# PMIC.net
KiCad netlist of a schematic drawn in Altium Designer
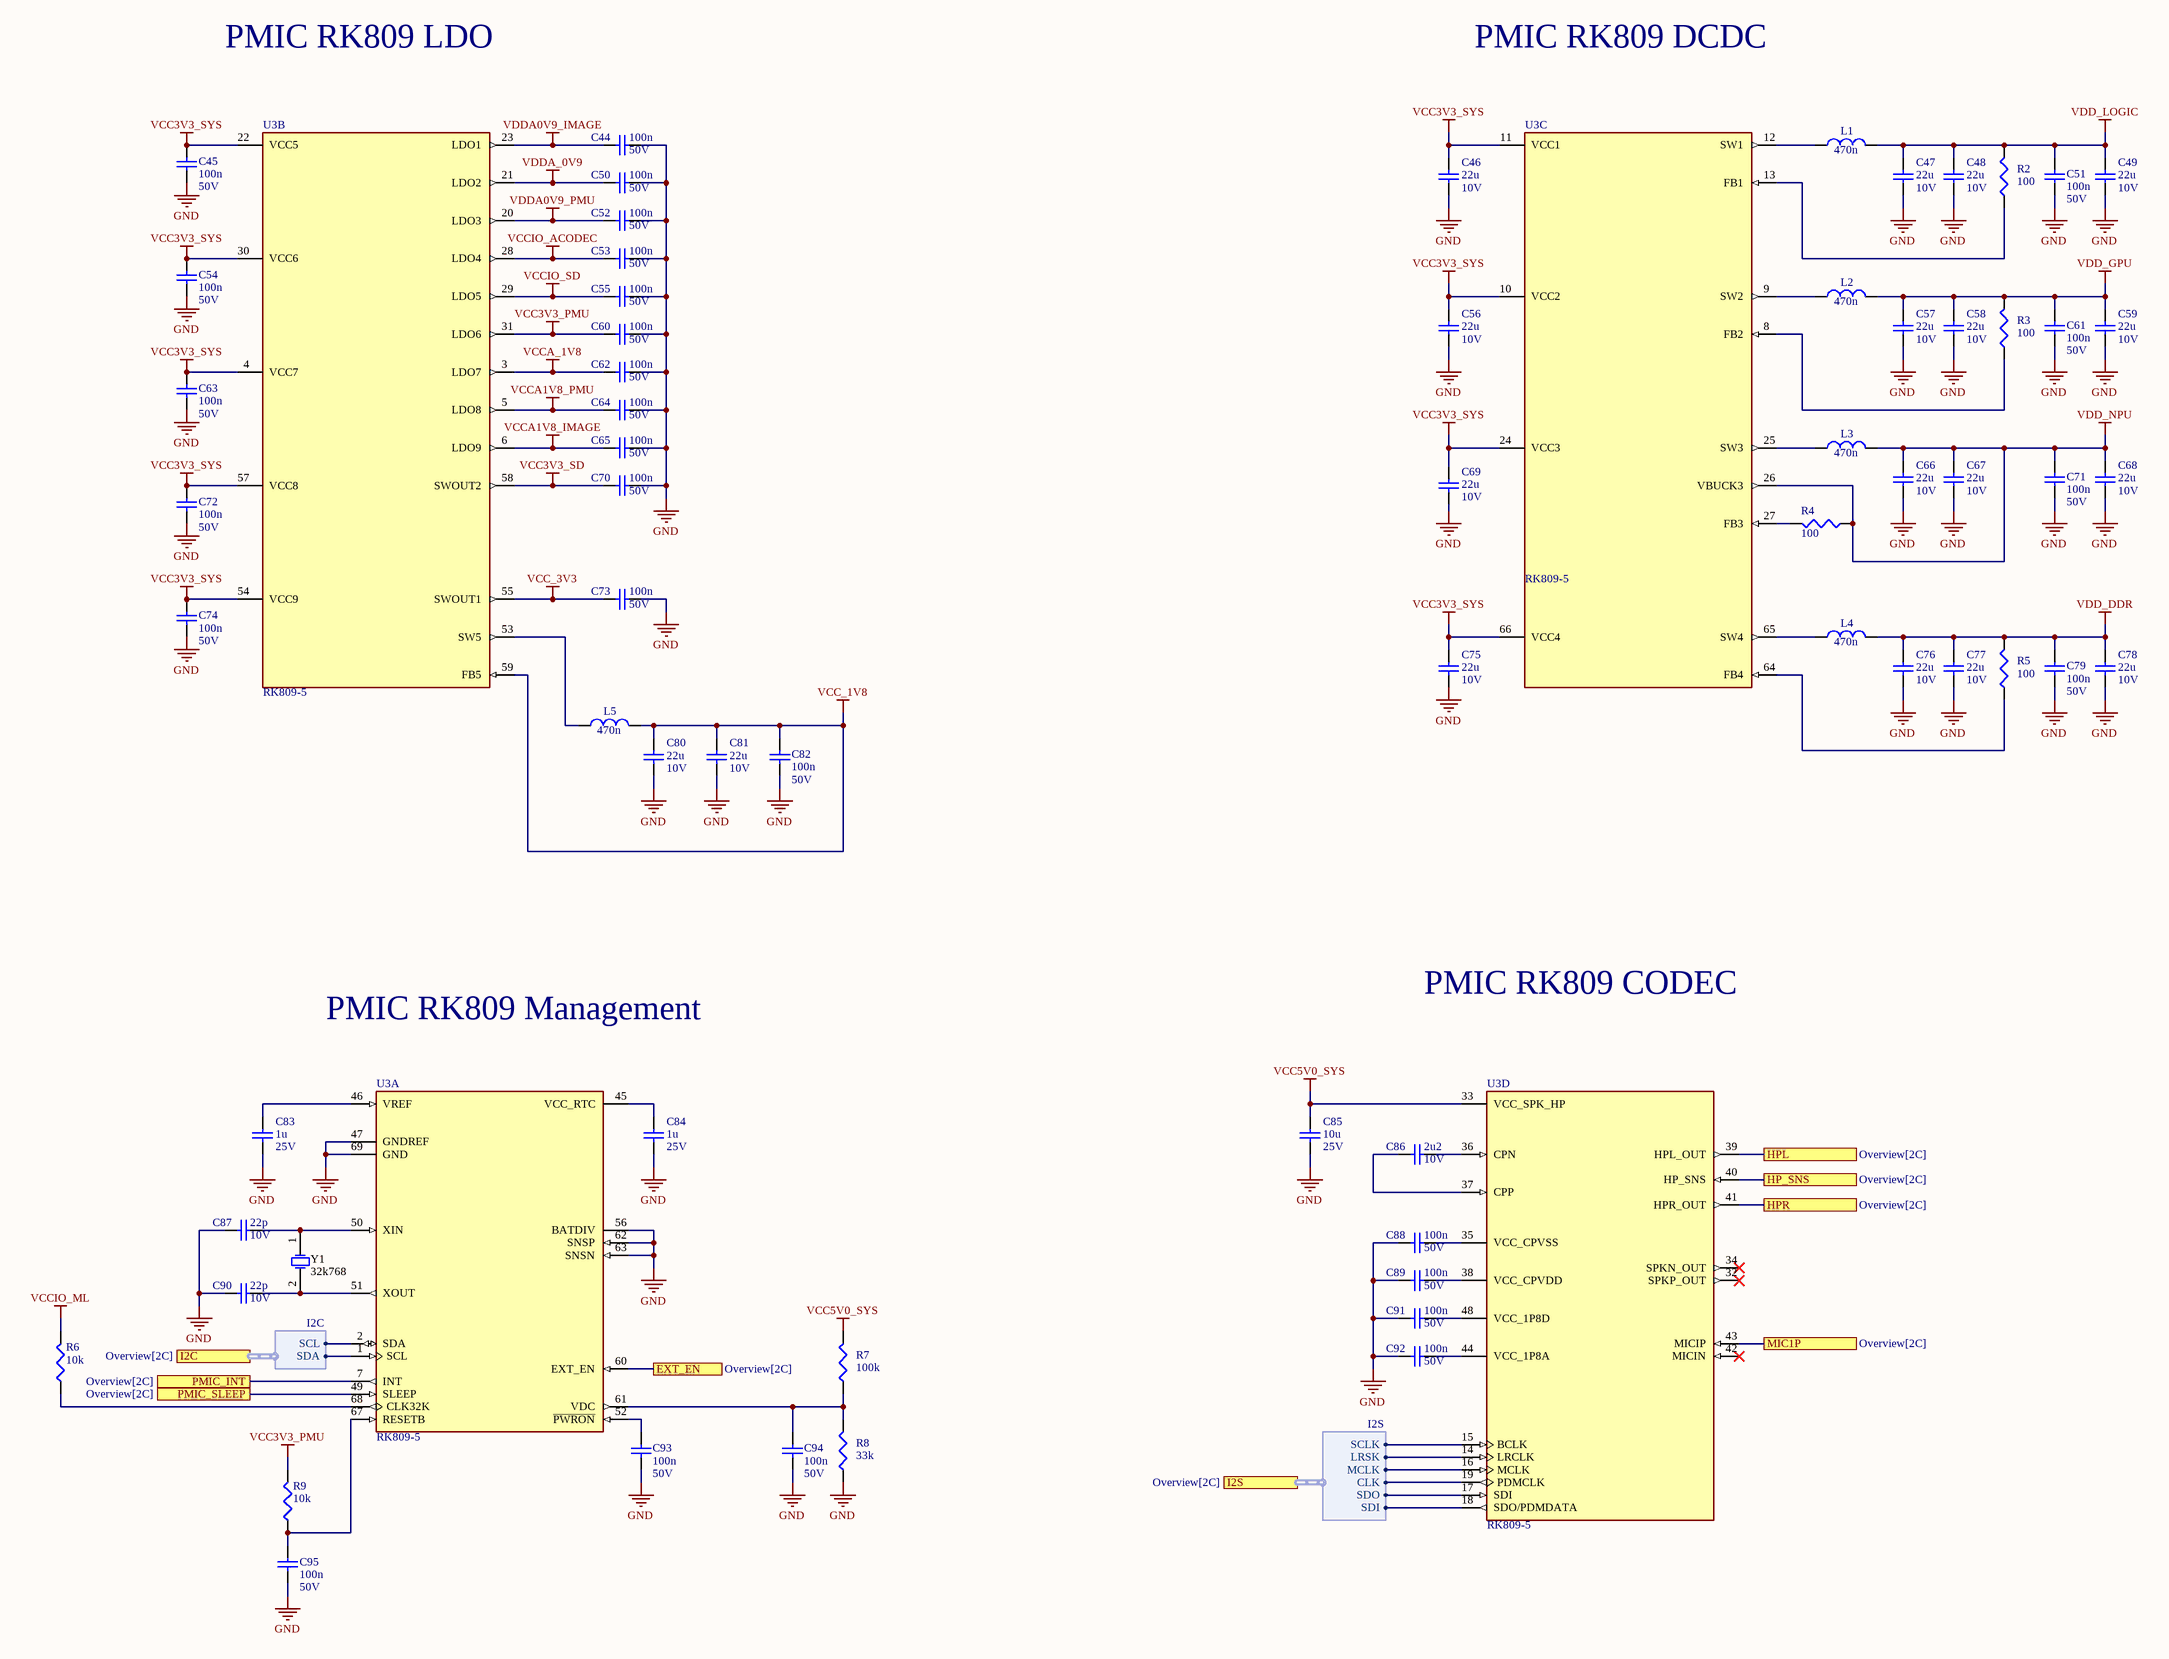
[diagram p0: PMIC.SchDoc]

(export (version "E")
  (design (tool "Eeschema 10.0.6"))
  (components
    (comp (ref "C44")
      (value "100n")
      (footprint "GRM155R71H104KE14D")
      (description "CAP 100N 50V X7R 0402")
      (fields (field (name "VOLTAGE") "50V") (field (name "Comment") "GRM155R71H104KE14D"))
      (libsource (lib "PersonalAltiumLibrary") (part "GRM155R71H104KE14D"))
    )
    (comp (ref "C45")
      (value "100n")
      (footprint "GRM155R71H104KE14D")
      (description "CAP 100N 50V X7R 0402")
      (fields (field (name "VOLTAGE") "50V") (field (name "Comment") "GRM155R71H104KE14D"))
      (libsource (lib "PersonalAltiumLibrary") (part "GRM155R71H104KE14D"))
    )
    (comp (ref "C46")
      (value "22u")
      (footprint "GRM188R61A226ME15D")
      (description "CAP 22U 10V X5R 0603")
      (fields (field (name "VOLTAGE") "10V") (field (name "Comment") "GRM188R61A226ME15D"))
      (libsource (lib "PersonalAltiumLibrary") (part "GRM188R61A226ME15D"))
    )
    (comp (ref "C47")
      (value "22u")
      (footprint "GRM188R61A226ME15D")
      (description "CAP 22U 10V X5R 0603")
      (fields (field (name "VOLTAGE") "10V") (field (name "Comment") "GRM188R61A226ME15D"))
      (libsource (lib "PersonalAltiumLibrary") (part "GRM188R61A226ME15D"))
    )
    (comp (ref "C48")
      (value "22u")
      (footprint "GRM188R61A226ME15D")
      (description "CAP 22U 10V X5R 0603")
      (fields (field (name "VOLTAGE") "10V") (field (name "Comment") "GRM188R61A226ME15D"))
      (libsource (lib "PersonalAltiumLibrary") (part "GRM188R61A226ME15D"))
    )
    (comp (ref "C49")
      (value "22u")
      (footprint "GRM188R61A226ME15D")
      (description "CAP 22U 10V X5R 0603")
      (fields (field (name "VOLTAGE") "10V") (field (name "Comment") "GRM188R61A226ME15D"))
      (libsource (lib "PersonalAltiumLibrary") (part "GRM188R61A226ME15D"))
    )
    (comp (ref "C50")
      (value "100n")
      (footprint "GRM155R71H104KE14D")
      (description "CAP 100N 50V X7R 0402")
      (fields (field (name "VOLTAGE") "50V") (field (name "Comment") "GRM155R71H104KE14D"))
      (libsource (lib "PersonalAltiumLibrary") (part "GRM155R71H104KE14D"))
    )
    (comp (ref "C51")
      (value "100n")
      (footprint "GRM155R71H104KE14D")
      (description "CAP 100N 50V X7R 0402")
      (fields (field (name "VOLTAGE") "50V") (field (name "Comment") "GRM155R71H104KE14D"))
      (libsource (lib "PersonalAltiumLibrary") (part "GRM155R71H104KE14D"))
    )
    (comp (ref "C52")
      (value "100n")
      (footprint "GRM155R71H104KE14D")
      (description "CAP 100N 50V X7R 0402")
      (fields (field (name "VOLTAGE") "50V") (field (name "Comment") "GRM155R71H104KE14D"))
      (libsource (lib "PersonalAltiumLibrary") (part "GRM155R71H104KE14D"))
    )
    (comp (ref "C53")
      (value "100n")
      (footprint "GRM155R71H104KE14D")
      (description "CAP 100N 50V X7R 0402")
      (fields (field (name "VOLTAGE") "50V") (field (name "Comment") "GRM155R71H104KE14D"))
      (libsource (lib "PersonalAltiumLibrary") (part "GRM155R71H104KE14D"))
    )
    (comp (ref "C54")
      (value "100n")
      (footprint "GRM155R71H104KE14D")
      (description "CAP 100N 50V X7R 0402")
      (fields (field (name "VOLTAGE") "50V") (field (name "Comment") "GRM155R71H104KE14D"))
      (libsource (lib "PersonalAltiumLibrary") (part "GRM155R71H104KE14D"))
    )
    (comp (ref "C55")
      (value "100n")
      (footprint "GRM155R71H104KE14D")
      (description "CAP 100N 50V X7R 0402")
      (fields (field (name "VOLTAGE") "50V") (field (name "Comment") "GRM155R71H104KE14D"))
      (libsource (lib "PersonalAltiumLibrary") (part "GRM155R71H104KE14D"))
    )
    (comp (ref "C56")
      (value "22u")
      (footprint "GRM188R61A226ME15D")
      (description "CAP 22U 10V X5R 0603")
      (fields (field (name "VOLTAGE") "10V") (field (name "Comment") "GRM188R61A226ME15D"))
      (libsource (lib "PersonalAltiumLibrary") (part "GRM188R61A226ME15D"))
    )
    (comp (ref "C57")
      (value "22u")
      (footprint "GRM188R61A226ME15D")
      (description "CAP 22U 10V X5R 0603")
      (fields (field (name "VOLTAGE") "10V") (field (name "Comment") "GRM188R61A226ME15D"))
      (libsource (lib "PersonalAltiumLibrary") (part "GRM188R61A226ME15D"))
    )
    (comp (ref "C58")
      (value "22u")
      (footprint "GRM188R61A226ME15D")
      (description "CAP 22U 10V X5R 0603")
      (fields (field (name "VOLTAGE") "10V") (field (name "Comment") "GRM188R61A226ME15D"))
      (libsource (lib "PersonalAltiumLibrary") (part "GRM188R61A226ME15D"))
    )
    (comp (ref "C59")
      (value "22u")
      (footprint "GRM188R61A226ME15D")
      (description "CAP 22U 10V X5R 0603")
      (fields (field (name "VOLTAGE") "10V") (field (name "Comment") "GRM188R61A226ME15D"))
      (libsource (lib "PersonalAltiumLibrary") (part "GRM188R61A226ME15D"))
    )
    (comp (ref "C60")
      (value "100n")
      (footprint "GRM155R71H104KE14D")
      (description "CAP 100N 50V X7R 0402")
      (fields (field (name "VOLTAGE") "50V") (field (name "Comment") "GRM155R71H104KE14D"))
      (libsource (lib "PersonalAltiumLibrary") (part "GRM155R71H104KE14D"))
    )
    (comp (ref "C61")
      (value "100n")
      (footprint "GRM155R71H104KE14D")
      (description "CAP 100N 50V X7R 0402")
      (fields (field (name "VOLTAGE") "50V") (field (name "Comment") "GRM155R71H104KE14D"))
      (libsource (lib "PersonalAltiumLibrary") (part "GRM155R71H104KE14D"))
    )
    (comp (ref "C62")
      (value "100n")
      (footprint "GRM155R71H104KE14D")
      (description "CAP 100N 50V X7R 0402")
      (fields (field (name "VOLTAGE") "50V") (field (name "Comment") "GRM155R71H104KE14D"))
      (libsource (lib "PersonalAltiumLibrary") (part "GRM155R71H104KE14D"))
    )
    (comp (ref "C63")
      (value "100n")
      (footprint "GRM155R71H104KE14D")
      (description "CAP 100N 50V X7R 0402")
      (fields (field (name "VOLTAGE") "50V") (field (name "Comment") "GRM155R71H104KE14D"))
      (libsource (lib "PersonalAltiumLibrary") (part "GRM155R71H104KE14D"))
    )
    (comp (ref "C64")
      (value "100n")
      (footprint "GRM155R71H104KE14D")
      (description "CAP 100N 50V X7R 0402")
      (fields (field (name "VOLTAGE") "50V") (field (name "Comment") "GRM155R71H104KE14D"))
      (libsource (lib "PersonalAltiumLibrary") (part "GRM155R71H104KE14D"))
    )
    (comp (ref "C65")
      (value "100n")
      (footprint "GRM155R71H104KE14D")
      (description "CAP 100N 50V X7R 0402")
      (fields (field (name "VOLTAGE") "50V") (field (name "Comment") "GRM155R71H104KE14D"))
      (libsource (lib "PersonalAltiumLibrary") (part "GRM155R71H104KE14D"))
    )
    (comp (ref "C66")
      (value "22u")
      (footprint "GRM188R61A226ME15D")
      (description "CAP 22U 10V X5R 0603")
      (fields (field (name "VOLTAGE") "10V") (field (name "Comment") "GRM188R61A226ME15D"))
      (libsource (lib "PersonalAltiumLibrary") (part "GRM188R61A226ME15D"))
    )
    (comp (ref "C67")
      (value "22u")
      (footprint "GRM188R61A226ME15D")
      (description "CAP 22U 10V X5R 0603")
      (fields (field (name "VOLTAGE") "10V") (field (name "Comment") "GRM188R61A226ME15D"))
      (libsource (lib "PersonalAltiumLibrary") (part "GRM188R61A226ME15D"))
    )
    (comp (ref "C68")
      (value "22u")
      (footprint "GRM188R61A226ME15D")
      (description "CAP 22U 10V X5R 0603")
      (fields (field (name "VOLTAGE") "10V") (field (name "Comment") "GRM188R61A226ME15D"))
      (libsource (lib "PersonalAltiumLibrary") (part "GRM188R61A226ME15D"))
    )
    (comp (ref "C69")
      (value "22u")
      (footprint "GRM188R61A226ME15D")
      (description "CAP 22U 10V X5R 0603")
      (fields (field (name "VOLTAGE") "10V") (field (name "Comment") "GRM188R61A226ME15D"))
      (libsource (lib "PersonalAltiumLibrary") (part "GRM188R61A226ME15D"))
    )
    (comp (ref "C70")
      (value "100n")
      (footprint "GRM155R71H104KE14D")
      (description "CAP 100N 50V X7R 0402")
      (fields (field (name "VOLTAGE") "50V") (field (name "Comment") "GRM155R71H104KE14D"))
      (libsource (lib "PersonalAltiumLibrary") (part "GRM155R71H104KE14D"))
    )
    (comp (ref "C71")
      (value "100n")
      (footprint "GRM155R71H104KE14D")
      (description "CAP 100N 50V X7R 0402")
      (fields (field (name "VOLTAGE") "50V") (field (name "Comment") "GRM155R71H104KE14D"))
      (libsource (lib "PersonalAltiumLibrary") (part "GRM155R71H104KE14D"))
    )
    (comp (ref "C72")
      (value "100n")
      (footprint "GRM155R71H104KE14D")
      (description "CAP 100N 50V X7R 0402")
      (fields (field (name "VOLTAGE") "50V") (field (name "Comment") "GRM155R71H104KE14D"))
      (libsource (lib "PersonalAltiumLibrary") (part "GRM155R71H104KE14D"))
    )
    (comp (ref "C73")
      (value "100n")
      (footprint "GRM155R71H104KE14D")
      (description "CAP 100N 50V X7R 0402")
      (fields (field (name "VOLTAGE") "50V") (field (name "Comment") "GRM155R71H104KE14D"))
      (libsource (lib "PersonalAltiumLibrary") (part "GRM155R71H104KE14D"))
    )
    (comp (ref "C74")
      (value "100n")
      (footprint "GRM155R71H104KE14D")
      (description "CAP 100N 50V X7R 0402")
      (fields (field (name "VOLTAGE") "50V") (field (name "Comment") "GRM155R71H104KE14D"))
      (libsource (lib "PersonalAltiumLibrary") (part "GRM155R71H104KE14D"))
    )
    (comp (ref "C75")
      (value "22u")
      (footprint "GRM188R61A226ME15D")
      (description "CAP 22U 10V X5R 0603")
      (fields (field (name "VOLTAGE") "10V") (field (name "Comment") "GRM188R61A226ME15D"))
      (libsource (lib "PersonalAltiumLibrary") (part "GRM188R61A226ME15D"))
    )
    (comp (ref "C76")
      (value "22u")
      (footprint "GRM188R61A226ME15D")
      (description "CAP 22U 10V X5R 0603")
      (fields (field (name "VOLTAGE") "10V") (field (name "Comment") "GRM188R61A226ME15D"))
      (libsource (lib "PersonalAltiumLibrary") (part "GRM188R61A226ME15D"))
    )
    (comp (ref "C77")
      (value "22u")
      (footprint "GRM188R61A226ME15D")
      (description "CAP 22U 10V X5R 0603")
      (fields (field (name "VOLTAGE") "10V") (field (name "Comment") "GRM188R61A226ME15D"))
      (libsource (lib "PersonalAltiumLibrary") (part "GRM188R61A226ME15D"))
    )
    (comp (ref "C78")
      (value "22u")
      (footprint "GRM188R61A226ME15D")
      (description "CAP 22U 10V X5R 0603")
      (fields (field (name "VOLTAGE") "10V") (field (name "Comment") "GRM188R61A226ME15D"))
      (libsource (lib "PersonalAltiumLibrary") (part "GRM188R61A226ME15D"))
    )
    (comp (ref "C79")
      (value "100n")
      (footprint "GRM155R71H104KE14D")
      (description "CAP 100N 50V X7R 0402")
      (fields (field (name "VOLTAGE") "50V") (field (name "Comment") "GRM155R71H104KE14D"))
      (libsource (lib "PersonalAltiumLibrary") (part "GRM155R71H104KE14D"))
    )
    (comp (ref "C80")
      (value "22u")
      (footprint "GRM188R61A226ME15D")
      (description "CAP 22U 10V X5R 0603")
      (fields (field (name "VOLTAGE") "10V") (field (name "Comment") "GRM188R61A226ME15D"))
      (libsource (lib "PersonalAltiumLibrary") (part "GRM188R61A226ME15D"))
    )
    (comp (ref "C81")
      (value "22u")
      (footprint "GRM188R61A226ME15D")
      (description "CAP 22U 10V X5R 0603")
      (fields (field (name "VOLTAGE") "10V") (field (name "Comment") "GRM188R61A226ME15D"))
      (libsource (lib "PersonalAltiumLibrary") (part "GRM188R61A226ME15D"))
    )
    (comp (ref "C82")
      (value "100n")
      (footprint "GRM155R71H104KE14D")
      (description "CAP 100N 50V X7R 0402")
      (fields (field (name "VOLTAGE") "50V") (field (name "Comment") "GRM155R71H104KE14D"))
      (libsource (lib "PersonalAltiumLibrary") (part "GRM155R71H104KE14D"))
    )
    (comp (ref "C83")
      (value "1u")
      (footprint "GRM155R61E105KA12D")
      (description "CAP 1U 25V X5R 0402")
      (fields (field (name "VOLTAGE") "25V") (field (name "Comment") "GRM155R61E105KA12D"))
      (libsource (lib "PersonalAltiumLibrary") (part "GRM155R61E105KA12D"))
    )
    (comp (ref "C84")
      (value "1u")
      (footprint "GRM155R61E105KA12D")
      (description "CAP 1U 25V X5R 0402")
      (fields (field (name "VOLTAGE") "25V") (field (name "Comment") "GRM155R61E105KA12D"))
      (libsource (lib "PersonalAltiumLibrary") (part "GRM155R61E105KA12D"))
    )
    (comp (ref "C85")
      (value "10u")
      (description "CAP 10U 25V X5R 0603")
      (fields (field (name "VOLTAGE") "25V") (field (name "Comment") "GRM188R61E106MA73D"))
      (libsource (lib "PersonalAltiumLibrary") (part "GRM188R61E106MA73D"))
    )
    (comp (ref "C86")
      (value "2u2")
      (footprint "GRM155R60J475ME47D")
      (description "CAP 2.2U 6.3V X5R 0402")
      (fields (field (name "VOLTAGE") "10V") (field (name "Comment") "Capacitor 2u2"))
      (libsource (lib "PersonalAltiumLibrary") (part "Capacitor 2u2"))
    )
    (comp (ref "C87")
      (value "22p")
      (footprint "GRM155R60J475ME47D")
      (description "CAP 22P 6.3V X5R 0402")
      (fields (field (name "VOLTAGE") "10V") (field (name "Comment") "CAP 22P"))
      (libsource (lib "PersonalAltiumLibrary") (part "CAP 22P"))
    )
    (comp (ref "C88")
      (value "100n")
      (footprint "GRM155R71H104KE14D")
      (description "CAP 100N 50V X7R 0402")
      (fields (field (name "VOLTAGE") "50V") (field (name "Comment") "GRM155R71H104KE14D"))
      (libsource (lib "PersonalAltiumLibrary") (part "GRM155R71H104KE14D"))
    )
    (comp (ref "C89")
      (value "100n")
      (footprint "GRM155R71H104KE14D")
      (description "CAP 100N 50V X7R 0402")
      (fields (field (name "VOLTAGE") "50V") (field (name "Comment") "GRM155R71H104KE14D"))
      (libsource (lib "PersonalAltiumLibrary") (part "GRM155R71H104KE14D"))
    )
    (comp (ref "C90")
      (value "22p")
      (footprint "GRM155R60J475ME47D")
      (description "CAP 22P 6.3V X5R 0402")
      (fields (field (name "VOLTAGE") "10V") (field (name "Comment") "CAP 22P"))
      (libsource (lib "PersonalAltiumLibrary") (part "CAP 22P"))
    )
    (comp (ref "C91")
      (value "100n")
      (footprint "GRM155R71H104KE14D")
      (description "CAP 100N 50V X7R 0402")
      (fields (field (name "VOLTAGE") "50V") (field (name "Comment") "GRM155R71H104KE14D"))
      (libsource (lib "PersonalAltiumLibrary") (part "GRM155R71H104KE14D"))
    )
    (comp (ref "C92")
      (value "100n")
      (footprint "GRM155R71H104KE14D")
      (description "CAP 100N 50V X7R 0402")
      (fields (field (name "VOLTAGE") "50V") (field (name "Comment") "GRM155R71H104KE14D"))
      (libsource (lib "PersonalAltiumLibrary") (part "GRM155R71H104KE14D"))
    )
    (comp (ref "C93")
      (value "100n")
      (footprint "GRM155R71H104KE14D")
      (description "CAP 100N 50V X7R 0402")
      (fields (field (name "VOLTAGE") "50V") (field (name "Comment") "GRM155R71H104KE14D"))
      (libsource (lib "PersonalAltiumLibrary") (part "GRM155R71H104KE14D"))
    )
    (comp (ref "C94")
      (value "100n")
      (footprint "GRM155R71H104KE14D")
      (description "CAP 100N 50V X7R 0402")
      (fields (field (name "VOLTAGE") "50V") (field (name "Comment") "GRM155R71H104KE14D"))
      (libsource (lib "PersonalAltiumLibrary") (part "GRM155R71H104KE14D"))
    )
    (comp (ref "C95")
      (value "100n")
      (footprint "GRM155R71H104KE14D")
      (description "CAP 100N 50V X7R 0402")
      (fields (field (name "VOLTAGE") "50V") (field (name "Comment") "GRM155R71H104KE14D"))
      (libsource (lib "PersonalAltiumLibrary") (part "GRM155R71H104KE14D"))
    )
    (comp (ref "L1")
      (value "470n")
      (description "IND 470N 4.05A 0806")
      (fields (field (name "Comment") "MCS20FC-R47MHC"))
      (libsource (lib "PersonalAltiumLibrary") (part "MCS20FC-R47MHC"))
    )
    (comp (ref "L2")
      (value "470n")
      (description "IND 470N 4.05A 0806")
      (fields (field (name "Comment") "MCS20FC-R47MHC"))
      (libsource (lib "PersonalAltiumLibrary") (part "MCS20FC-R47MHC"))
    )
    (comp (ref "L3")
      (value "470n")
      (description "IND 470N 4.05A 0806")
      (fields (field (name "Comment") "MCS20FC-R47MHC"))
      (libsource (lib "PersonalAltiumLibrary") (part "MCS20FC-R47MHC"))
    )
    (comp (ref "L4")
      (value "470n")
      (description "IND 470N 4.05A 0806")
      (fields (field (name "Comment") "MCS20FC-R47MHC"))
      (libsource (lib "PersonalAltiumLibrary") (part "MCS20FC-R47MHC"))
    )
    (comp (ref "L5")
      (value "470n")
      (description "IND 470N 4.05A 0806")
      (fields (field (name "Comment") "MCS20FC-R47MHC"))
      (libsource (lib "PersonalAltiumLibrary") (part "MCS20FC-R47MHC"))
    )
    (comp (ref "R2")
      (value "100")
      (footprint "RC0402FR-07100RL")
      (description "RES 100 1% 0402")
      (fields (field (name "Comment") "RC0402FR-07100RL"))
      (libsource (lib "PersonalAltiumLibrary") (part "RC0402FR-07100RL"))
    )
    (comp (ref "R3")
      (value "100")
      (footprint "RC0402FR-07100RL")
      (description "RES 100 1% 0402")
      (fields (field (name "Comment") "RC0402FR-07100RL"))
      (libsource (lib "PersonalAltiumLibrary") (part "RC0402FR-07100RL"))
    )
    (comp (ref "R4")
      (value "100")
      (footprint "RC0402FR-07100RL")
      (description "RES 100 1% 0402")
      (fields (field (name "Comment") "RC0402FR-07100RL"))
      (libsource (lib "PersonalAltiumLibrary") (part "RC0402FR-07100RL"))
    )
    (comp (ref "R5")
      (value "100")
      (footprint "RC0402FR-07100RL")
      (description "RES 100 1% 0402")
      (fields (field (name "Comment") "RC0402FR-07100RL"))
      (libsource (lib "PersonalAltiumLibrary") (part "RC0402FR-07100RL"))
    )
    (comp (ref "R6")
      (value "10k")
      (footprint "RC0402FR-0718KL")
      (description "RES 10k 1% 62.5mW 0402")
      (fields (field (name "Comment") "RES 10k"))
      (libsource (lib "PersonalAltiumLibrary") (part "RES 10k"))
    )
    (comp (ref "R7")
      (value "100k")
      (footprint "RC0402FR-07100KL")
      (description "RES 100k 1% 62.5mW 0402")
      (fields (field (name "Comment") "RC0402FR-07100KL"))
      (libsource (lib "PersonalAltiumLibrary") (part "RC0402FR-07100KL"))
    )
    (comp (ref "R8")
      (value "33k")
      (footprint "RC0402FR-07100KL")
      (description "RES 33k 1% 62.5mW 0402")
      (fields (field (name "Comment") "RES 33k"))
      (libsource (lib "PersonalAltiumLibrary") (part "RES 33k"))
    )
    (comp (ref "R9")
      (value "10k")
      (footprint "RC0402FR-0718KL")
      (description "RES 10k 1% 62.5mW 0402")
      (fields (field (name "Comment") "RES 10k"))
      (libsource (lib "PersonalAltiumLibrary") (part "RES 10k"))
    )
    (comp (ref "U3")
      (value "RK809-5")
      (footprint "RK809-5")
      (fields (field (name "MF") "Fuzhou Rockchip Electronics Co") (field (name "MP") "RK809-1"))
      (libsource (lib "PersonalAltiumLibrary") (part "RK809-5"))
    )
    (comp (ref "Y1") (value "32k768") (libsource (lib "PersonalAltiumLibrary") (part "32.768 Crystal")))
  )
  (nets
    (net (code "3") (name "/CLK") (class "Default")
      (node (ref "U3") (pin "19") (pinfunction "PDMCLK_19") (pintype "output"))
    )
    (net (code "4") (name "/EXT_EN") (class "Default")
      (node (ref "U3") (pin "60") (pinfunction "EXT_EN_60") (pintype "input"))
    )
    (net (code "5") (name "/HPL") (class "Default")
      (node (ref "U3") (pin "39") (pinfunction "HPL_OUT_39") (pintype "output"))
    )
    (net (code "6") (name "/HPR") (class "Default")
      (node (ref "U3") (pin "41") (pinfunction "HPR_OUT_41") (pintype "output"))
    )
    (net (code "7") (name "/HP_SNS") (class "Default")
      (node (ref "U3") (pin "40") (pinfunction "HP_SNS_40") (pintype "input"))
    )
    (net (code "8") (name "/LRSK") (class "Default")
      (node (ref "U3") (pin "14") (pinfunction "LRCLK_14") (pintype "input"))
    )
    (net (code "9") (name "/MCLK") (class "Default")
      (node (ref "U3") (pin "16") (pinfunction "MCLK_16") (pintype "input"))
    )
    (net (code "10") (name "/MIC1P") (class "Default")
      (node (ref "U3") (pin "43") (pinfunction "MICIP_43") (pintype "input"))
    )
    (net (code "11") (name "/PMIC_INT") (class "Default")
      (node (ref "U3") (pin "7") (pinfunction "INT_7") (pintype "output"))
    )
    (net (code "12") (name "/PMIC_SLEEP") (class "Default")
      (node (ref "U3") (pin "49") (pinfunction "SLEEP_49") (pintype "input"))
    )
    (net (code "13") (name "/SCL") (class "Default")
      (node (ref "U3") (pin "2") (pinfunction "SDA_2") (pintype "bidirectional"))
    )
    (net (code "14") (name "/SCLK") (class "Default")
      (node (ref "U3") (pin "15") (pinfunction "BCLK_15") (pintype "input"))
    )
    (net (code "15") (name "/SDA") (class "Default")
      (node (ref "U3") (pin "1") (pinfunction "SCL_1") (pintype "input"))
    )
    (net (code "16") (name "/SDI") (class "Default")
      (node (ref "U3") (pin "18") (pinfunction "SDO/PDMDATA_18") (pintype "output"))
    )
    (net (code "17") (name "/SDO") (class "Default")
      (node (ref "U3") (pin "17") (pinfunction "SDI_17") (pintype "input"))
    )
    (net (code "20") (name "GND") (class "Default")
      (node (ref "C44") (pin "2") (pinfunction "2_2") (pintype "passive"))
      (node (ref "C45") (pin "1") (pinfunction "1_1") (pintype "passive"))
      (node (ref "C46") (pin "2") (pinfunction "2_2") (pintype "passive"))
      (node (ref "C47") (pin "2") (pinfunction "2_2") (pintype "passive"))
      (node (ref "C48") (pin "2") (pinfunction "2_2") (pintype "passive"))
      (node (ref "C49") (pin "2") (pinfunction "2_2") (pintype "passive"))
      (node (ref "C50") (pin "2") (pinfunction "2_2") (pintype "passive"))
      (node (ref "C51") (pin "2") (pinfunction "2_2") (pintype "passive"))
      (node (ref "C52") (pin "2") (pinfunction "2_2") (pintype "passive"))
      (node (ref "C53") (pin "2") (pinfunction "2_2") (pintype "passive"))
      (node (ref "C54") (pin "1") (pinfunction "1_1") (pintype "passive"))
      (node (ref "C55") (pin "2") (pinfunction "2_2") (pintype "passive"))
      (node (ref "C56") (pin "2") (pinfunction "2_2") (pintype "passive"))
      (node (ref "C57") (pin "2") (pinfunction "2_2") (pintype "passive"))
      (node (ref "C58") (pin "2") (pinfunction "2_2") (pintype "passive"))
      (node (ref "C59") (pin "2") (pinfunction "2_2") (pintype "passive"))
      (node (ref "C60") (pin "2") (pinfunction "2_2") (pintype "passive"))
      (node (ref "C61") (pin "2") (pinfunction "2_2") (pintype "passive"))
      (node (ref "C62") (pin "2") (pinfunction "2_2") (pintype "passive"))
      (node (ref "C63") (pin "1") (pinfunction "1_1") (pintype "passive"))
      (node (ref "C64") (pin "2") (pinfunction "2_2") (pintype "passive"))
      (node (ref "C65") (pin "2") (pinfunction "2_2") (pintype "passive"))
      (node (ref "C66") (pin "2") (pinfunction "2_2") (pintype "passive"))
      (node (ref "C67") (pin "2") (pinfunction "2_2") (pintype "passive"))
      (node (ref "C68") (pin "2") (pinfunction "2_2") (pintype "passive"))
      (node (ref "C69") (pin "2") (pinfunction "2_2") (pintype "passive"))
      (node (ref "C70") (pin "2") (pinfunction "2_2") (pintype "passive"))
      (node (ref "C71") (pin "2") (pinfunction "2_2") (pintype "passive"))
      (node (ref "C72") (pin "1") (pinfunction "1_1") (pintype "passive"))
      (node (ref "C73") (pin "2") (pinfunction "2_2") (pintype "passive"))
      (node (ref "C74") (pin "1") (pinfunction "1_1") (pintype "passive"))
      (node (ref "C75") (pin "2") (pinfunction "2_2") (pintype "passive"))
      (node (ref "C76") (pin "2") (pinfunction "2_2") (pintype "passive"))
      (node (ref "C77") (pin "2") (pinfunction "2_2") (pintype "passive"))
      (node (ref "C78") (pin "2") (pinfunction "2_2") (pintype "passive"))
      (node (ref "C79") (pin "2") (pinfunction "2_2") (pintype "passive"))
      (node (ref "C80") (pin "2") (pinfunction "2_2") (pintype "passive"))
      (node (ref "C81") (pin "2") (pinfunction "2_2") (pintype "passive"))
      (node (ref "C82") (pin "2") (pinfunction "2_2") (pintype "passive"))
      (node (ref "C83") (pin "2") (pinfunction "2_2") (pintype "passive"))
      (node (ref "C84") (pin "2") (pinfunction "2_2") (pintype "passive"))
      (node (ref "C85") (pin "2") (pinfunction "2_2") (pintype "passive"))
      (node (ref "C87") (pin "1") (pinfunction "1_1") (pintype "passive"))
      (node (ref "C88") (pin "1") (pinfunction "1_1") (pintype "passive"))
      (node (ref "C89") (pin "1") (pinfunction "1_1") (pintype "passive"))
      (node (ref "C90") (pin "1") (pinfunction "1_1") (pintype "passive"))
      (node (ref "C91") (pin "1") (pinfunction "1_1") (pintype "passive"))
      (node (ref "C92") (pin "1") (pinfunction "1_1") (pintype "passive"))
      (node (ref "C93") (pin "2") (pinfunction "2_2") (pintype "passive"))
      (node (ref "C94") (pin "2") (pinfunction "2_2") (pintype "passive"))
      (node (ref "C95") (pin "2") (pinfunction "2_2") (pintype "passive"))
      (node (ref "R8") (pin "2") (pinfunction "2_2") (pintype "passive"))
      (node (ref "U3") (pin "47") (pinfunction "GNDREF_47") (pintype "power_in"))
      (node (ref "U3") (pin "56") (pinfunction "BATDIV_56") (pintype "power_in"))
      (node (ref "U3") (pin "62") (pinfunction "SNSP_62") (pintype "input"))
      (node (ref "U3") (pin "63") (pinfunction "SNSN_63") (pintype "input"))
      (node (ref "U3") (pin "69") (pinfunction "GND_69") (pintype "power_in"))
    )
    (net (code "21") (name "Net-(U3A-CLK32K)") (class "Default")
      (node (ref "R6") (pin "2") (pinfunction "2_2") (pintype "passive"))
      (node (ref "U3") (pin "68") (pinfunction "CLK32K_68") (pintype "output"))
    )
    (net (code "22") (name "Net-(U3A-RESETB)") (class "Default")
      (node (ref "C95") (pin "1") (pinfunction "1_1") (pintype "passive"))
      (node (ref "R9") (pin "2") (pinfunction "2_2") (pintype "passive"))
      (node (ref "U3") (pin "67") (pinfunction "RESETB_67") (pintype "input"))
    )
    (net (code "23") (name "Net-(U3A-VCC_RTC)") (class "Default")
      (node (ref "C84") (pin "1") (pinfunction "1_1") (pintype "passive"))
      (node (ref "U3") (pin "45") (pinfunction "VCC_RTC_45") (pintype "power_in"))
    )
    (net (code "24") (name "Net-(U3A-VDC)") (class "Default")
      (node (ref "C94") (pin "1") (pinfunction "1_1") (pintype "passive"))
      (node (ref "R7") (pin "2") (pinfunction "2_2") (pintype "passive"))
      (node (ref "R8") (pin "1") (pinfunction "1_1") (pintype "passive"))
      (node (ref "U3") (pin "61") (pinfunction "VDC_61") (pintype "output"))
    )
    (net (code "25") (name "Net-(U3A-VREF)") (class "Default")
      (node (ref "C83") (pin "1") (pinfunction "1_1") (pintype "passive"))
      (node (ref "U3") (pin "46") (pinfunction "VREF_46") (pintype "input"))
    )
    (net (code "26") (name "Net-(U3A-XIN)") (class "Default")
      (node (ref "C87") (pin "2") (pinfunction "2_2") (pintype "passive"))
      (node (ref "U3") (pin "50") (pinfunction "XIN_50") (pintype "input"))
      (node (ref "Y1") (pin "1") (pinfunction "1_1") (pintype "passive"))
    )
    (net (code "27") (name "Net-(U3A-XOUT)") (class "Default")
      (node (ref "C90") (pin "2") (pinfunction "2_2") (pintype "passive"))
      (node (ref "U3") (pin "51") (pinfunction "XOUT_51") (pintype "output"))
      (node (ref "Y1") (pin "2") (pinfunction "2_2") (pintype "passive"))
    )
    (net (code "28") (name "Net-(U3A-~{PWRON})") (class "Default")
      (node (ref "C93") (pin "1") (pinfunction "1_1") (pintype "passive"))
      (node (ref "U3") (pin "52") (pinfunction "~{PWRON}_52") (pintype "input"))
    )
    (net (code "29") (name "Net-(U3B-SW5)") (class "Default")
      (node (ref "L5") (pin "1") (pinfunction "1_1") (pintype "passive"))
      (node (ref "U3") (pin "53") (pinfunction "SW5_53") (pintype "output"))
    )
    (net (code "30") (name "Net-(U3C-FB1)") (class "Default")
      (node (ref "R2") (pin "2") (pinfunction "2_2") (pintype "passive"))
      (node (ref "U3") (pin "13") (pinfunction "FB1_13") (pintype "input"))
    )
    (net (code "31") (name "Net-(U3C-FB2)") (class "Default")
      (node (ref "R3") (pin "2") (pinfunction "2_2") (pintype "passive"))
      (node (ref "U3") (pin "8") (pinfunction "FB2_8") (pintype "input"))
    )
    (net (code "32") (name "Net-(U3C-FB3)") (class "Default")
      (node (ref "R4") (pin "1") (pinfunction "1_1") (pintype "passive"))
      (node (ref "U3") (pin "27") (pinfunction "FB3_27") (pintype "input"))
    )
    (net (code "33") (name "Net-(U3C-FB4)") (class "Default")
      (node (ref "R5") (pin "2") (pinfunction "2_2") (pintype "passive"))
      (node (ref "U3") (pin "64") (pinfunction "FB4_64") (pintype "input"))
    )
    (net (code "34") (name "Net-(U3C-SW1)") (class "Default")
      (node (ref "L1") (pin "1") (pinfunction "1_1") (pintype "passive"))
      (node (ref "U3") (pin "12") (pinfunction "SW1_12") (pintype "output"))
    )
    (net (code "35") (name "Net-(U3C-SW2)") (class "Default")
      (node (ref "L2") (pin "1") (pinfunction "1_1") (pintype "passive"))
      (node (ref "U3") (pin "9") (pinfunction "SW2_9") (pintype "output"))
    )
    (net (code "36") (name "Net-(U3C-SW3)") (class "Default")
      (node (ref "L3") (pin "1") (pinfunction "1_1") (pintype "passive"))
      (node (ref "U3") (pin "25") (pinfunction "SW3_25") (pintype "output"))
    )
    (net (code "37") (name "Net-(U3C-SW4)") (class "Default")
      (node (ref "L4") (pin "1") (pinfunction "1_1") (pintype "passive"))
      (node (ref "U3") (pin "65") (pinfunction "SW4_65") (pintype "output"))
    )
    (net (code "38") (name "Net-(U3D-CPN)") (class "Default")
      (node (ref "C86") (pin "2") (pinfunction "2_2") (pintype "passive"))
      (node (ref "U3") (pin "36") (pinfunction "CPN_36") (pintype "input"))
    )
    (net (code "39") (name "Net-(U3D-CPP)") (class "Default")
      (node (ref "C86") (pin "1") (pinfunction "1_1") (pintype "passive"))
      (node (ref "U3") (pin "37") (pinfunction "CPP_37") (pintype "input"))
    )
    (net (code "40") (name "Net-(U3D-VCC_1P8A)") (class "Default")
      (node (ref "C92") (pin "2") (pinfunction "2_2") (pintype "passive"))
      (node (ref "U3") (pin "44") (pinfunction "VCC_1P8A_44") (pintype "power_in"))
    )
    (net (code "41") (name "Net-(U3D-VCC_1P8D)") (class "Default")
      (node (ref "C91") (pin "2") (pinfunction "2_2") (pintype "passive"))
      (node (ref "U3") (pin "48") (pinfunction "VCC_1P8D_48") (pintype "power_in"))
    )
    (net (code "42") (name "Net-(U3D-VCC_CPVDD)") (class "Default")
      (node (ref "C89") (pin "2") (pinfunction "2_2") (pintype "passive"))
      (node (ref "U3") (pin "38") (pinfunction "VCC_CPVDD_38") (pintype "power_in"))
    )
    (net (code "43") (name "Net-(U3D-VCC_CPVSS)") (class "Default")
      (node (ref "C88") (pin "2") (pinfunction "2_2") (pintype "passive"))
      (node (ref "U3") (pin "35") (pinfunction "VCC_CPVSS_35") (pintype "power_in"))
    )
    (net (code "44") (name "VCC3V3_PMU") (class "Default")
      (node (ref "C60") (pin "1") (pinfunction "1_1") (pintype "passive"))
      (node (ref "R9") (pin "1") (pinfunction "1_1") (pintype "passive"))
      (node (ref "U3") (pin "31") (pinfunction "LDO6_31") (pintype "output"))
    )
    (net (code "45") (name "VCC3V3_SD") (class "Default")
      (node (ref "C70") (pin "1") (pinfunction "1_1") (pintype "passive"))
      (node (ref "U3") (pin "58") (pinfunction "SWOUT2_58") (pintype "output"))
    )
    (net (code "46") (name "VCC3V3_SYS") (class "Default")
      (node (ref "C45") (pin "2") (pinfunction "2_2") (pintype "passive"))
      (node (ref "C46") (pin "1") (pinfunction "1_1") (pintype "passive"))
      (node (ref "C54") (pin "2") (pinfunction "2_2") (pintype "passive"))
      (node (ref "C56") (pin "1") (pinfunction "1_1") (pintype "passive"))
      (node (ref "C63") (pin "2") (pinfunction "2_2") (pintype "passive"))
      (node (ref "C69") (pin "1") (pinfunction "1_1") (pintype "passive"))
      (node (ref "C72") (pin "2") (pinfunction "2_2") (pintype "passive"))
      (node (ref "C74") (pin "2") (pinfunction "2_2") (pintype "passive"))
      (node (ref "C75") (pin "1") (pinfunction "1_1") (pintype "passive"))
      (node (ref "U3") (pin "10") (pinfunction "VCC2_10") (pintype "power_in"))
      (node (ref "U3") (pin "11") (pinfunction "VCC1_11") (pintype "power_in"))
      (node (ref "U3") (pin "22") (pinfunction "VCC5_22") (pintype "power_in"))
      (node (ref "U3") (pin "24") (pinfunction "VCC3_24") (pintype "power_in"))
      (node (ref "U3") (pin "30") (pinfunction "VCC6_30") (pintype "power_in"))
      (node (ref "U3") (pin "4") (pinfunction "VCC7_4") (pintype "power_in"))
      (node (ref "U3") (pin "54") (pinfunction "VCC9_54") (pintype "power_in"))
      (node (ref "U3") (pin "57") (pinfunction "VCC8_57") (pintype "power_in"))
      (node (ref "U3") (pin "66") (pinfunction "VCC4_66") (pintype "power_in"))
    )
    (net (code "47") (name "VCC5V0_SYS") (class "Default")
      (node (ref "C85") (pin "1") (pinfunction "1_1") (pintype "passive"))
      (node (ref "R7") (pin "1") (pinfunction "1_1") (pintype "passive"))
      (node (ref "U3") (pin "33") (pinfunction "VCC_SPK_HP_33") (pintype "power_in"))
    )
    (net (code "48") (name "VCCA1V8_IMAGE") (class "Default")
      (node (ref "C65") (pin "1") (pinfunction "1_1") (pintype "passive"))
      (node (ref "U3") (pin "6") (pinfunction "LDO9_6") (pintype "output"))
    )
    (net (code "49") (name "VCCA1V8_PMU") (class "Default")
      (node (ref "C64") (pin "1") (pinfunction "1_1") (pintype "passive"))
      (node (ref "U3") (pin "5") (pinfunction "LDO8_5") (pintype "output"))
    )
    (net (code "50") (name "VCCA_1V8") (class "Default")
      (node (ref "C62") (pin "1") (pinfunction "1_1") (pintype "passive"))
      (node (ref "U3") (pin "3") (pinfunction "LDO7_3") (pintype "output"))
    )
    (net (code "51") (name "VCCIO_ACODEC") (class "Default")
      (node (ref "C53") (pin "1") (pinfunction "1_1") (pintype "passive"))
      (node (ref "U3") (pin "28") (pinfunction "LDO4_28") (pintype "output"))
    )
    (net (code "52") (name "VCCIO_ML") (class "Default")
      (node (ref "R6") (pin "1") (pinfunction "1_1") (pintype "passive"))
    )
    (net (code "53") (name "VCCIO_SD") (class "Default")
      (node (ref "C55") (pin "1") (pinfunction "1_1") (pintype "passive"))
      (node (ref "U3") (pin "29") (pinfunction "LDO5_29") (pintype "output"))
    )
    (net (code "54") (name "VCC_1V8") (class "Default")
      (node (ref "C80") (pin "1") (pinfunction "1_1") (pintype "passive"))
      (node (ref "C81") (pin "1") (pinfunction "1_1") (pintype "passive"))
      (node (ref "C82") (pin "1") (pinfunction "1_1") (pintype "passive"))
      (node (ref "L5") (pin "2") (pinfunction "2_2") (pintype "passive"))
      (node (ref "U3") (pin "59") (pinfunction "FB5_59") (pintype "input"))
    )
    (net (code "55") (name "VCC_3V3") (class "Default")
      (node (ref "C73") (pin "1") (pinfunction "1_1") (pintype "passive"))
      (node (ref "U3") (pin "55") (pinfunction "SWOUT1_55") (pintype "output"))
    )
    (net (code "56") (name "VDDA0V9_IMAGE") (class "Default")
      (node (ref "C44") (pin "1") (pinfunction "1_1") (pintype "passive"))
      (node (ref "U3") (pin "23") (pinfunction "LDO1_23") (pintype "output"))
    )
    (net (code "57") (name "VDDA0V9_PMU") (class "Default")
      (node (ref "C52") (pin "1") (pinfunction "1_1") (pintype "passive"))
      (node (ref "U3") (pin "20") (pinfunction "LDO3_20") (pintype "output"))
    )
    (net (code "58") (name "VDDA_0V9") (class "Default")
      (node (ref "C50") (pin "1") (pinfunction "1_1") (pintype "passive"))
      (node (ref "U3") (pin "21") (pinfunction "LDO2_21") (pintype "output"))
    )
    (net (code "59") (name "VDD_DDR") (class "Default")
      (node (ref "C76") (pin "1") (pinfunction "1_1") (pintype "passive"))
      (node (ref "C77") (pin "1") (pinfunction "1_1") (pintype "passive"))
      (node (ref "C78") (pin "1") (pinfunction "1_1") (pintype "passive"))
      (node (ref "C79") (pin "1") (pinfunction "1_1") (pintype "passive"))
      (node (ref "L4") (pin "2") (pinfunction "2_2") (pintype "passive"))
      (node (ref "R5") (pin "1") (pinfunction "1_1") (pintype "passive"))
    )
    (net (code "60") (name "VDD_GPU") (class "Default")
      (node (ref "C57") (pin "1") (pinfunction "1_1") (pintype "passive"))
      (node (ref "C58") (pin "1") (pinfunction "1_1") (pintype "passive"))
      (node (ref "C59") (pin "1") (pinfunction "1_1") (pintype "passive"))
      (node (ref "C61") (pin "1") (pinfunction "1_1") (pintype "passive"))
      (node (ref "L2") (pin "2") (pinfunction "2_2") (pintype "passive"))
      (node (ref "R3") (pin "1") (pinfunction "1_1") (pintype "passive"))
    )
    (net (code "61") (name "VDD_LOGIC") (class "Default")
      (node (ref "C47") (pin "1") (pinfunction "1_1") (pintype "passive"))
      (node (ref "C48") (pin "1") (pinfunction "1_1") (pintype "passive"))
      (node (ref "C49") (pin "1") (pinfunction "1_1") (pintype "passive"))
      (node (ref "C51") (pin "1") (pinfunction "1_1") (pintype "passive"))
      (node (ref "L1") (pin "2") (pinfunction "2_2") (pintype "passive"))
      (node (ref "R2") (pin "1") (pinfunction "1_1") (pintype "passive"))
    )
    (net (code "62") (name "VDD_NPU") (class "Default")
      (node (ref "C66") (pin "1") (pinfunction "1_1") (pintype "passive"))
      (node (ref "C67") (pin "1") (pinfunction "1_1") (pintype "passive"))
      (node (ref "C68") (pin "1") (pinfunction "1_1") (pintype "passive"))
      (node (ref "C71") (pin "1") (pinfunction "1_1") (pintype "passive"))
      (node (ref "L3") (pin "2") (pinfunction "2_2") (pintype "passive"))
      (node (ref "R4") (pin "2") (pinfunction "2_2") (pintype "passive"))
      (node (ref "U3") (pin "26") (pinfunction "VBUCK3_26") (pintype "output"))
    )
    (net (code "63") (name "unconnected-(U3D-MICIN-Pad42)") (class "Default")
      (node (ref "U3") (pin "42") (pinfunction "MICIN_42") (pintype "input+no_connect"))
    )
    (net (code "64") (name "unconnected-(U3D-SPKN_OUT-Pad34)") (class "Default")
      (node (ref "U3") (pin "34") (pinfunction "SPKN_OUT_34") (pintype "output+no_connect"))
    )
    (net (code "65") (name "unconnected-(U3D-SPKP_OUT-Pad32)") (class "Default")
      (node (ref "U3") (pin "32") (pinfunction "SPKP_OUT_32") (pintype "output+no_connect"))
    )
  )
)
